# Shield_Telemetria2.net
KiCad netlist of a schematic drawn in EAGLE
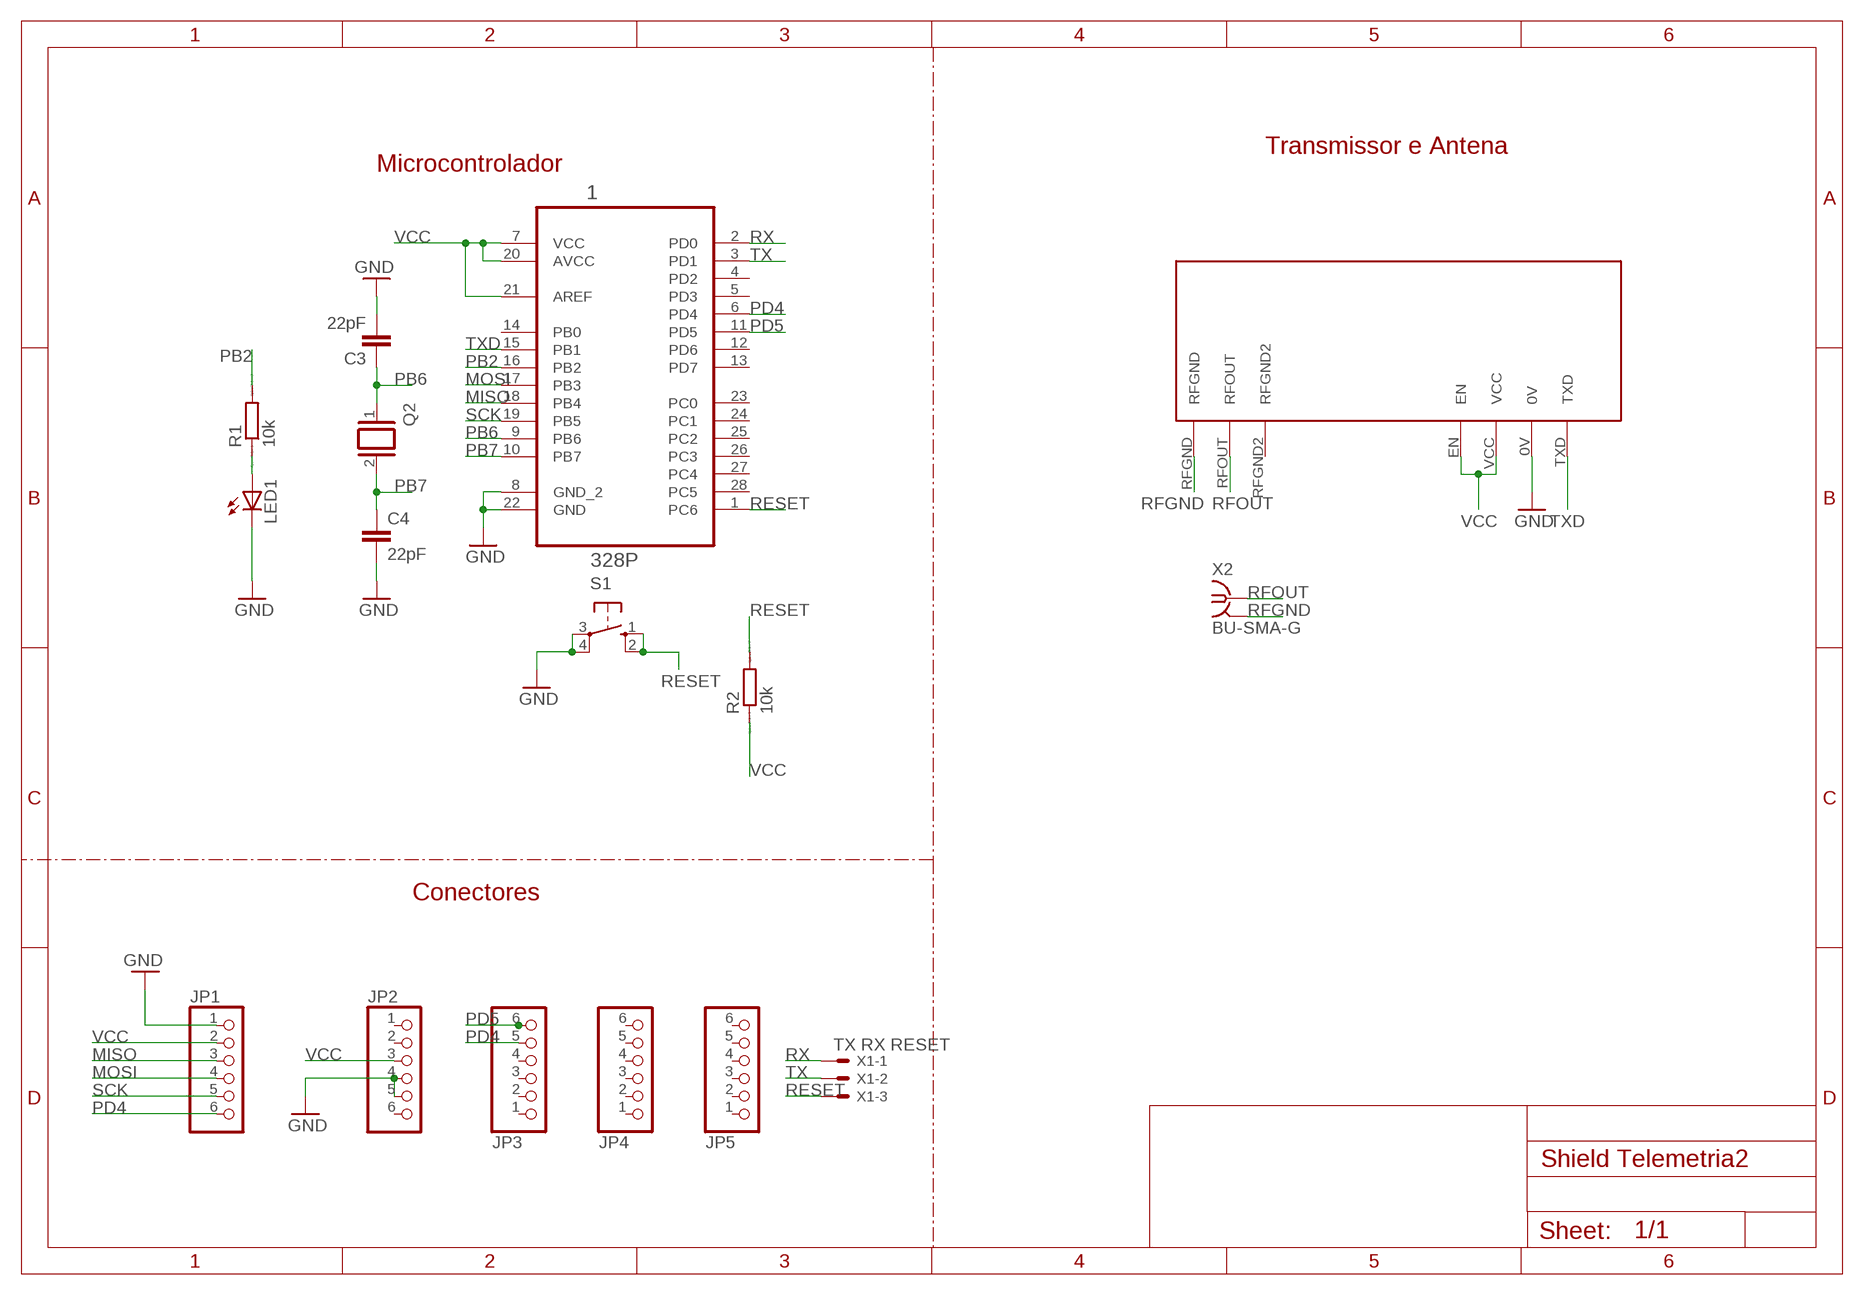
[diagram p0: schematic, sheet 1]

(export (version "E")
  (design (tool "Eeschema 10.0.6"))
  (components
    (comp (ref "1")
      (value "328P")
      (footprint "eagle-import:DIP254P762X457-28")
      (fields (field (name "MPN") "ATMEGA328P-PU"))
      (libsource (lib "eagle-import") (part "ATMEGA328P-PU"))
    )
    (comp (ref "C3")
      (value "22pF")
      (footprint "eagle-import:C5B4.5")
      (libsource (lib "eagle-import") (part "C5/4.5"))
    )
    (comp (ref "C4")
      (value "22pF")
      (footprint "eagle-import:C5B4.5")
      (libsource (lib "eagle-import") (part "C5/4.5"))
    )
    (comp (ref "JP1")
      (value "PINHD-1X6")
      (footprint "eagle-import:1X06")
      (libsource (lib "eagle-import") (part "PINHD-1X6"))
    )
    (comp (ref "JP2")
      (value "PINHD-1X6")
      (footprint "eagle-import:1X06")
      (libsource (lib "eagle-import") (part "pinhead_PINHD-1X6"))
    )
    (comp (ref "JP3")
      (value "PINHD-1X6")
      (footprint "eagle-import:1X06")
      (libsource (lib "eagle-import") (part "pinhead_PINHD-1X6"))
    )
    (comp (ref "JP4")
      (value "PINHD-1X6")
      (footprint "eagle-import:1X06")
      (libsource (lib "eagle-import") (part "pinhead_PINHD-1X6"))
    )
    (comp (ref "JP5")
      (value "PINHD-1X6")
      (footprint "eagle-import:1X06")
      (libsource (lib "eagle-import") (part "pinhead_PINHD-1X6"))
    )
    (comp (ref "LED1")
      (value "LED3MM")
      (footprint "eagle-import:LED3MM")
      (libsource (lib "eagle-import") (part "LED3MM"))
    )
    (comp (ref "Q2")
      (value "XTAL/S")
      (footprint "eagle-import:QS")
      (libsource (lib "eagle-import") (part "XTAL/S"))
    )
    (comp (ref "R1")
      (value "10k")
      (footprint "eagle-import:0207_10")
      (libsource (lib "eagle-import") (part "R0207/10"))
    )
    (comp (ref "R2")
      (value "10k")
      (footprint "eagle-import:0207_10")
      (libsource (lib "eagle-import") (part "R0207/10"))
    )
    (comp (ref "S1")
      (value "10-XX")
      (footprint "eagle-import:B3F-10XX")
      (fields (field (name "MPN") "B3F-1000"))
      (libsource (lib "eagle-import") (part "10-XX"))
    )
    (comp (ref "U$1")
      (value "NTX2")
      (footprint "eagle-import:NTX2")
      (libsource (lib "eagle-import") (part "NTX2"))
    )
    (comp (ref "X1")
      (value "TX RX RESET")
      (footprint "eagle-import:22-23-2031")
      (fields (field (name "MF") "MOLEX") (field (name "MPN") "22-23-2031"))
      (libsource (lib "eagle-import") (part "22-23-2031"))
    )
    (comp (ref "X2")
      (value "BU-SMA-G")
      (footprint "eagle-import:BU-SMA-G")
      (libsource (lib "eagle-import") (part "BU-SMA-G"))
    )
  )
  (nets
    (net (code "1") (name "/MISO") (class "Default")
      (node (ref "1") (pin "18") (pinfunction "PB4_18") (pintype "bidirectional"))
      (node (ref "JP1") (pin "3") (pinfunction "3_3") (pintype "passive"))
    )
    (net (code "2") (name "/MOSI") (class "Default")
      (node (ref "1") (pin "17") (pinfunction "PB3_17") (pintype "bidirectional"))
      (node (ref "JP1") (pin "4") (pinfunction "4_4") (pintype "passive"))
    )
    (net (code "3") (name "/PB2") (class "Default")
      (node (ref "1") (pin "16") (pinfunction "PB2_16") (pintype "bidirectional"))
      (node (ref "R1") (pin "2") (pinfunction "2_2") (pintype "passive"))
    )
    (net (code "4") (name "/PB6") (class "Default")
      (node (ref "1") (pin "9") (pinfunction "PB6_9") (pintype "bidirectional"))
      (node (ref "C3") (pin "1") (pinfunction "1_1") (pintype "passive"))
      (node (ref "Q2") (pin "1") (pinfunction "1_1") (pintype "passive"))
    )
    (net (code "5") (name "/PB7") (class "Default")
      (node (ref "1") (pin "10") (pinfunction "PB7_10") (pintype "bidirectional"))
      (node (ref "C4") (pin "1") (pinfunction "1_1") (pintype "passive"))
      (node (ref "Q2") (pin "2") (pinfunction "2_2") (pintype "passive"))
    )
    (net (code "6") (name "/PD4") (class "Default")
      (node (ref "1") (pin "6") (pinfunction "PD4_6") (pintype "bidirectional"))
      (node (ref "JP1") (pin "6") (pinfunction "6_6") (pintype "passive"))
      (node (ref "JP3") (pin "5") (pinfunction "5_5") (pintype "passive"))
    )
    (net (code "7") (name "/PD5") (class "Default")
      (node (ref "1") (pin "11") (pinfunction "PD5_11") (pintype "bidirectional"))
      (node (ref "JP3") (pin "6") (pinfunction "6_6") (pintype "passive"))
    )
    (net (code "8") (name "/RESET") (class "Default")
      (node (ref "1") (pin "1") (pinfunction "PC6_1") (pintype "bidirectional"))
      (node (ref "R2") (pin "2") (pinfunction "2_2") (pintype "passive"))
      (node (ref "S1") (pin "1") (pinfunction "S_1") (pintype "passive"))
      (node (ref "S1") (pin "2") (pinfunction "S1_2") (pintype "passive"))
      (node (ref "X1") (pin "3") (pinfunction "S_3") (pintype "passive"))
    )
    (net (code "9") (name "/RFGND") (class "Default")
      (node (ref "U$1") (pin "RFGND") (pinfunction "RFGND_RFGND") (pintype "bidirectional"))
      (node (ref "X2") (pin "2") (pinfunction "2_2") (pintype "passive"))
      (node (ref "X2") (pin "3") (pinfunction "2_3") (pintype "passive"))
      (node (ref "X2") (pin "4") (pinfunction "2_4") (pintype "passive"))
      (node (ref "X2") (pin "5") (pinfunction "2_5") (pintype "passive"))
    )
    (net (code "10") (name "/RFOUT") (class "Default")
      (node (ref "U$1") (pin "RFOUT") (pinfunction "RFOUT_RFOUT") (pintype "bidirectional"))
      (node (ref "X2") (pin "1") (pinfunction "1_1") (pintype "passive"))
    )
    (net (code "11") (name "/RX") (class "Default")
      (node (ref "1") (pin "2") (pinfunction "PD0_2") (pintype "bidirectional"))
      (node (ref "X1") (pin "1") (pinfunction "S_1") (pintype "passive"))
    )
    (net (code "12") (name "/SCK") (class "Default")
      (node (ref "1") (pin "19") (pinfunction "PB5_19") (pintype "bidirectional"))
      (node (ref "JP1") (pin "5") (pinfunction "5_5") (pintype "passive"))
    )
    (net (code "13") (name "/TX") (class "Default")
      (node (ref "1") (pin "3") (pinfunction "PD1_3") (pintype "bidirectional"))
      (node (ref "X1") (pin "2") (pinfunction "S_2") (pintype "passive"))
    )
    (net (code "14") (name "/TXD") (class "Default")
      (node (ref "1") (pin "15") (pinfunction "PB1_15") (pintype "bidirectional"))
      (node (ref "U$1") (pin "TXD") (pinfunction "TXD_TXD") (pintype "bidirectional"))
    )
    (net (code "15") (name "/VCC") (class "Default")
      (node (ref "1") (pin "20") (pinfunction "AVCC_20") (pintype "power_in"))
      (node (ref "1") (pin "21") (pinfunction "AREF_21") (pintype "input"))
      (node (ref "1") (pin "7") (pinfunction "VCC_7") (pintype "power_in"))
      (node (ref "JP1") (pin "2") (pinfunction "2_2") (pintype "passive"))
      (node (ref "JP2") (pin "3") (pinfunction "3_3") (pintype "passive"))
      (node (ref "R2") (pin "1") (pinfunction "1_1") (pintype "passive"))
      (node (ref "U$1") (pin "EN") (pinfunction "EN_EN") (pintype "bidirectional"))
      (node (ref "U$1") (pin "VCC") (pinfunction "VCC_VCC") (pintype "bidirectional"))
    )
    (net (code "16") (name "GND") (class "Default")
      (node (ref "1") (pin "22") (pinfunction "GND_22") (pintype "passive"))
      (node (ref "1") (pin "8") (pinfunction "GND_2_8") (pintype "passive"))
      (node (ref "C3") (pin "2") (pinfunction "2_2") (pintype "passive"))
      (node (ref "C4") (pin "2") (pinfunction "2_2") (pintype "passive"))
      (node (ref "JP1") (pin "1") (pinfunction "1_1") (pintype "passive"))
      (node (ref "JP2") (pin "4") (pinfunction "4_4") (pintype "passive"))
      (node (ref "JP2") (pin "5") (pinfunction "5_5") (pintype "passive"))
      (node (ref "LED1") (pin "K") (pinfunction "C_K") (pintype "passive"))
      (node (ref "S1") (pin "3") (pinfunction "P_3") (pintype "passive"))
      (node (ref "S1") (pin "4") (pinfunction "P1_4") (pintype "passive"))
      (node (ref "U$1") (pin "0V") (pinfunction "0V_0V") (pintype "bidirectional"))
    )
    (net (code "17") (name "Net-(LED1-PadA)") (class "Default")
      (node (ref "LED1") (pin "A") (pinfunction "A_A") (pintype "passive"))
      (node (ref "R1") (pin "1") (pinfunction "1_1") (pintype "passive"))
    )
    (net (code "18") (name "unconnected-(1-PB0-Pad14)") (class "Default")
      (node (ref "1") (pin "14") (pinfunction "PB0_14") (pintype "bidirectional"))
    )
    (net (code "19") (name "unconnected-(1-PC0-Pad23)") (class "Default")
      (node (ref "1") (pin "23") (pinfunction "PC0_23") (pintype "bidirectional"))
    )
    (net (code "20") (name "unconnected-(1-PC1-Pad24)") (class "Default")
      (node (ref "1") (pin "24") (pinfunction "PC1_24") (pintype "bidirectional"))
    )
    (net (code "21") (name "unconnected-(1-PC2-Pad25)") (class "Default")
      (node (ref "1") (pin "25") (pinfunction "PC2_25") (pintype "bidirectional"))
    )
    (net (code "22") (name "unconnected-(1-PC3-Pad26)") (class "Default")
      (node (ref "1") (pin "26") (pinfunction "PC3_26") (pintype "bidirectional"))
    )
    (net (code "23") (name "unconnected-(1-PC4-Pad27)") (class "Default")
      (node (ref "1") (pin "27") (pinfunction "PC4_27") (pintype "bidirectional"))
    )
    (net (code "24") (name "unconnected-(1-PC5-Pad28)") (class "Default")
      (node (ref "1") (pin "28") (pinfunction "PC5_28") (pintype "bidirectional"))
    )
    (net (code "25") (name "unconnected-(1-PD2-Pad4)") (class "Default")
      (node (ref "1") (pin "4") (pinfunction "PD2_4") (pintype "bidirectional"))
    )
    (net (code "26") (name "unconnected-(1-PD3-Pad5)") (class "Default")
      (node (ref "1") (pin "5") (pinfunction "PD3_5") (pintype "bidirectional"))
    )
    (net (code "27") (name "unconnected-(1-PD6-Pad12)") (class "Default")
      (node (ref "1") (pin "12") (pinfunction "PD6_12") (pintype "bidirectional"))
    )
    (net (code "28") (name "unconnected-(1-PD7-Pad13)") (class "Default")
      (node (ref "1") (pin "13") (pinfunction "PD7_13") (pintype "bidirectional"))
    )
    (net (code "29") (name "unconnected-(JP2-Pad1)") (class "Default")
      (node (ref "JP2") (pin "1") (pinfunction "1_1") (pintype "passive"))
    )
    (net (code "30") (name "unconnected-(JP2-Pad2)") (class "Default")
      (node (ref "JP2") (pin "2") (pinfunction "2_2") (pintype "passive"))
    )
    (net (code "31") (name "unconnected-(JP2-Pad6)") (class "Default")
      (node (ref "JP2") (pin "6") (pinfunction "6_6") (pintype "passive"))
    )
    (net (code "32") (name "unconnected-(JP3-Pad1)") (class "Default")
      (node (ref "JP3") (pin "1") (pinfunction "1_1") (pintype "passive"))
    )
    (net (code "33") (name "unconnected-(JP3-Pad2)") (class "Default")
      (node (ref "JP3") (pin "2") (pinfunction "2_2") (pintype "passive"))
    )
    (net (code "34") (name "unconnected-(JP3-Pad3)") (class "Default")
      (node (ref "JP3") (pin "3") (pinfunction "3_3") (pintype "passive"))
    )
    (net (code "35") (name "unconnected-(JP3-Pad4)") (class "Default")
      (node (ref "JP3") (pin "4") (pinfunction "4_4") (pintype "passive"))
    )
    (net (code "36") (name "unconnected-(JP4-Pad1)") (class "Default")
      (node (ref "JP4") (pin "1") (pinfunction "1_1") (pintype "passive"))
    )
    (net (code "37") (name "unconnected-(JP4-Pad2)") (class "Default")
      (node (ref "JP4") (pin "2") (pinfunction "2_2") (pintype "passive"))
    )
    (net (code "38") (name "unconnected-(JP4-Pad3)") (class "Default")
      (node (ref "JP4") (pin "3") (pinfunction "3_3") (pintype "passive"))
    )
    (net (code "39") (name "unconnected-(JP4-Pad4)") (class "Default")
      (node (ref "JP4") (pin "4") (pinfunction "4_4") (pintype "passive"))
    )
    (net (code "40") (name "unconnected-(JP4-Pad5)") (class "Default")
      (node (ref "JP4") (pin "5") (pinfunction "5_5") (pintype "passive"))
    )
    (net (code "41") (name "unconnected-(JP4-Pad6)") (class "Default")
      (node (ref "JP4") (pin "6") (pinfunction "6_6") (pintype "passive"))
    )
    (net (code "42") (name "unconnected-(JP5-Pad1)") (class "Default")
      (node (ref "JP5") (pin "1") (pinfunction "1_1") (pintype "passive"))
    )
    (net (code "43") (name "unconnected-(JP5-Pad2)") (class "Default")
      (node (ref "JP5") (pin "2") (pinfunction "2_2") (pintype "passive"))
    )
    (net (code "44") (name "unconnected-(JP5-Pad3)") (class "Default")
      (node (ref "JP5") (pin "3") (pinfunction "3_3") (pintype "passive"))
    )
    (net (code "45") (name "unconnected-(JP5-Pad4)") (class "Default")
      (node (ref "JP5") (pin "4") (pinfunction "4_4") (pintype "passive"))
    )
    (net (code "46") (name "unconnected-(JP5-Pad5)") (class "Default")
      (node (ref "JP5") (pin "5") (pinfunction "5_5") (pintype "passive"))
    )
    (net (code "47") (name "unconnected-(JP5-Pad6)") (class "Default")
      (node (ref "JP5") (pin "6") (pinfunction "6_6") (pintype "passive"))
    )
    (net (code "48") (name "unconnected-(U$1-PadRFGND2)") (class "Default")
      (node (ref "U$1") (pin "RFGND2") (pinfunction "RFGND2_RFGND2") (pintype "bidirectional"))
    )
  )
)
